# working.net
KiCad netlist of a schematic drawn in EAGLE
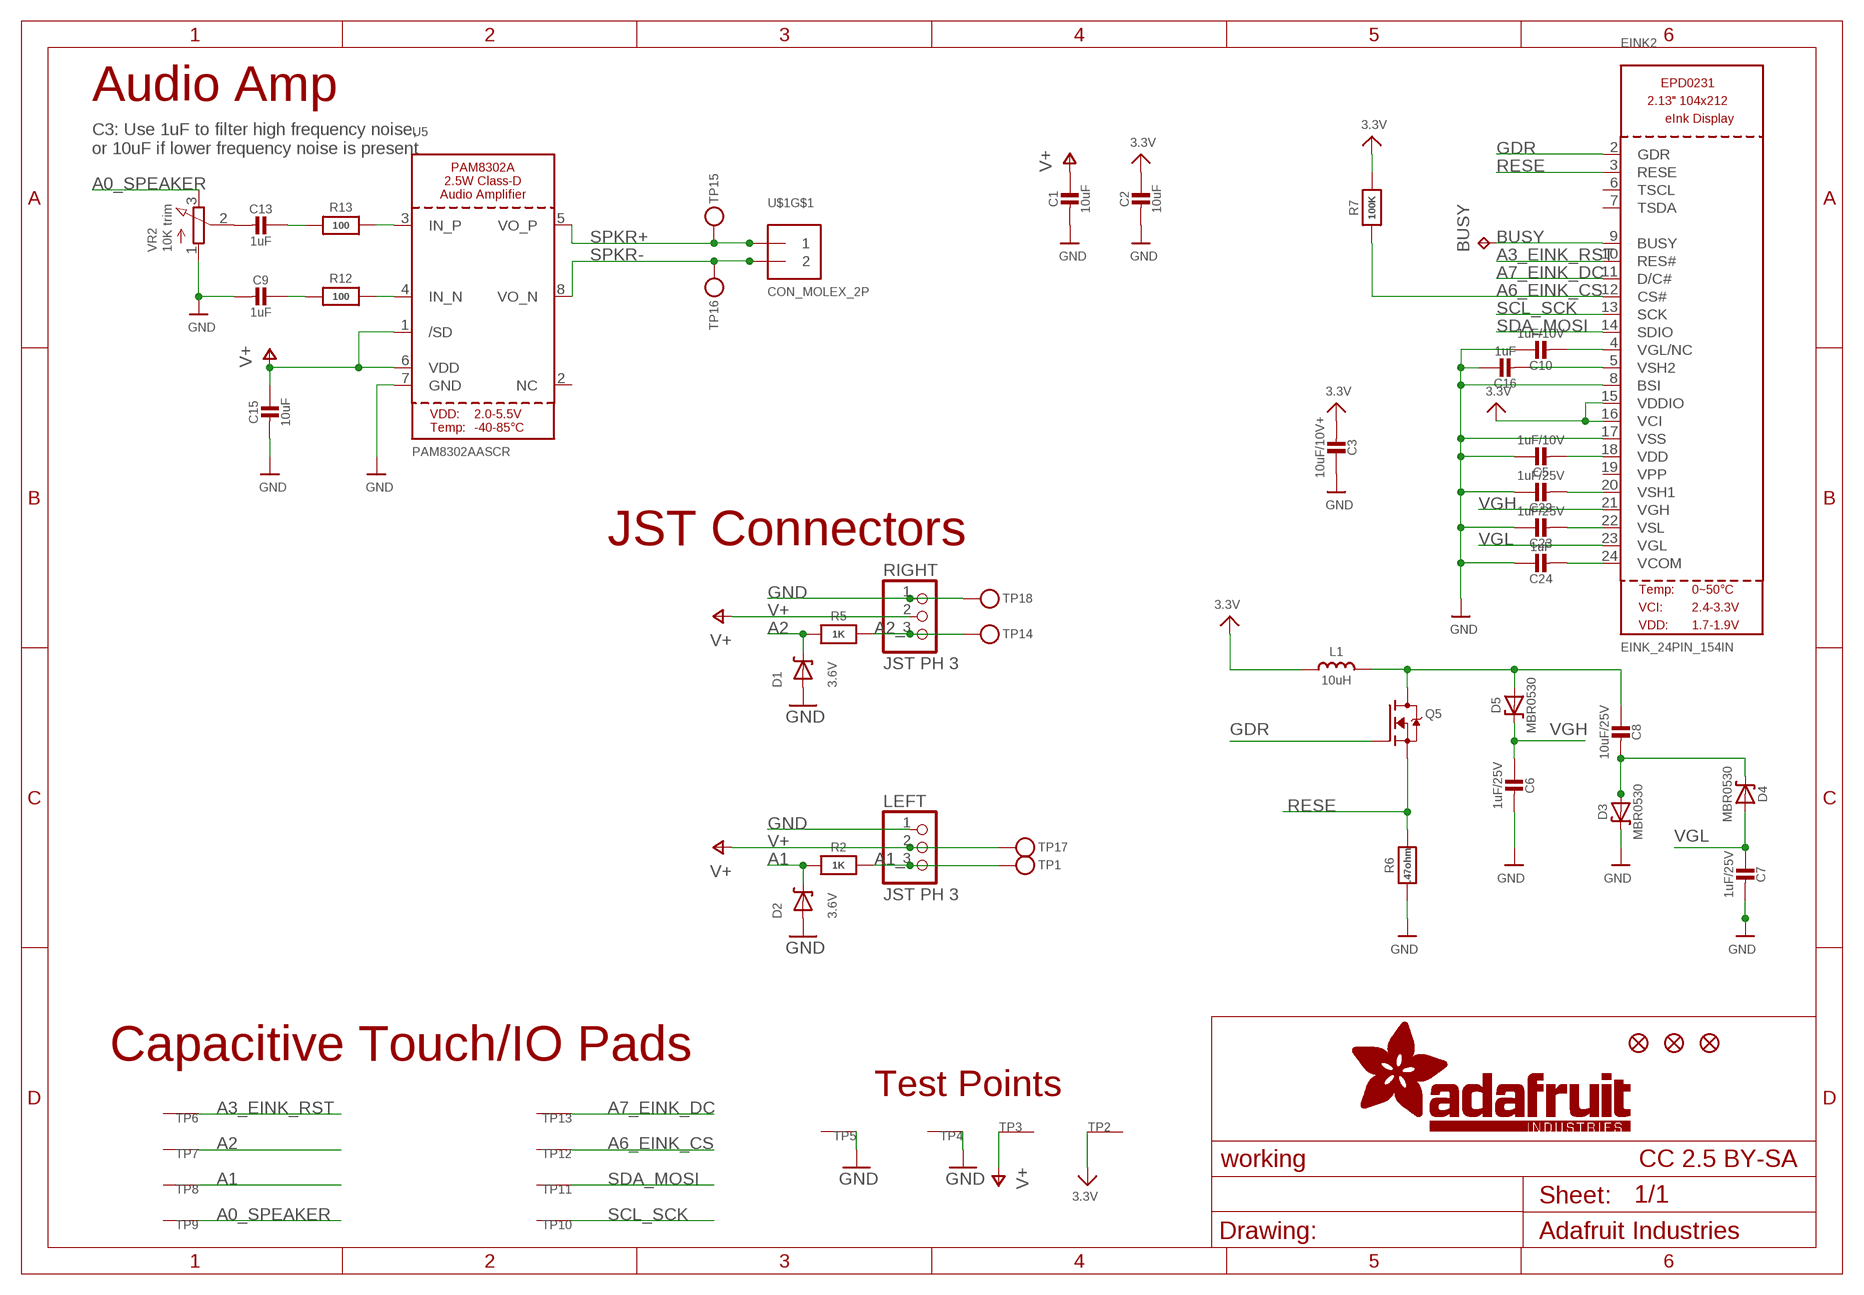
[diagram p0: schematic, sheet 1]

(export (version "E")
  (design (tool "Eeschema 10.0.6"))
  (components
    (comp (ref "BUSY")
      (value "TPTP15SQ")
      (footprint "eagle-import:TP15SQ")
      (libsource (lib "eagle-import") (part "TPTP15SQ"))
    )
    (comp (ref "C1")
      (value "10uF")
      (footprint "eagle-import:0805-NO")
      (libsource (lib "eagle-import") (part "CAP_CERAMIC0805-NOOUTLINE"))
    )
    (comp (ref "C2")
      (value "10uF")
      (footprint "eagle-import:0805-NO")
      (libsource (lib "eagle-import") (part "CAP_CERAMIC0805-NOOUTLINE"))
    )
    (comp (ref "C3")
      (value "10uF/10V+")
      (footprint "eagle-import:0805-NO")
      (libsource (lib "eagle-import") (part "CAP_CERAMIC0805-NOOUTLINE"))
    )
    (comp (ref "C5")
      (value "1uF/10V")
      (footprint "eagle-import:0805-NO")
      (libsource (lib "eagle-import") (part "CAP_CERAMIC0805-NOOUTLINE"))
    )
    (comp (ref "C6")
      (value "1uF/25V")
      (footprint "eagle-import:0805-NO")
      (libsource (lib "eagle-import") (part "CAP_CERAMIC0805-NOOUTLINE"))
    )
    (comp (ref "C7")
      (value "1uF/25V")
      (footprint "eagle-import:0805-NO")
      (libsource (lib "eagle-import") (part "CAP_CERAMIC0805-NOOUTLINE"))
    )
    (comp (ref "C8")
      (value "10uF/25V")
      (footprint "eagle-import:0805-NO")
      (libsource (lib "eagle-import") (part "CAP_CERAMIC0805-NOOUTLINE"))
    )
    (comp (ref "C9")
      (value "1uF")
      (footprint "eagle-import:0805-NO")
      (libsource (lib "eagle-import") (part "CAP_CERAMIC0805-NOOUTLINE"))
    )
    (comp (ref "C10")
      (value "1uF/10V")
      (footprint "eagle-import:0805-NO")
      (libsource (lib "eagle-import") (part "CAP_CERAMIC0805-NOOUTLINE"))
    )
    (comp (ref "C13")
      (value "1uF")
      (footprint "eagle-import:0805-NO")
      (libsource (lib "eagle-import") (part "CAP_CERAMIC0805-NOOUTLINE"))
    )
    (comp (ref "C15")
      (value "10uF")
      (footprint "eagle-import:0805-NO")
      (libsource (lib "eagle-import") (part "CAP_CERAMIC0805-NOOUTLINE"))
    )
    (comp (ref "C16")
      (value "1uF")
      (footprint "eagle-import:0805-NO")
      (libsource (lib "eagle-import") (part "CAP_CERAMIC0805-NOOUTLINE"))
    )
    (comp (ref "C22")
      (value "1uF/25V")
      (footprint "eagle-import:0805-NO")
      (libsource (lib "eagle-import") (part "CAP_CERAMIC0805-NOOUTLINE"))
    )
    (comp (ref "C23")
      (value "1uF/25V")
      (footprint "eagle-import:0805-NO")
      (libsource (lib "eagle-import") (part "CAP_CERAMIC0805-NOOUTLINE"))
    )
    (comp (ref "C24")
      (value "1uF")
      (footprint "eagle-import:0805-NO")
      (libsource (lib "eagle-import") (part "CAP_CERAMIC0805-NOOUTLINE"))
    )
    (comp (ref "D1")
      (value "3.6V")
      (footprint "eagle-import:SOD-323")
      (libsource (lib "eagle-import") (part "DIODE-ZENERSOD323"))
    )
    (comp (ref "D2")
      (value "3.6V")
      (footprint "eagle-import:SOD-323")
      (libsource (lib "eagle-import") (part "DIODE-ZENERSOD323"))
    )
    (comp (ref "D3")
      (value "MBR0530")
      (footprint "eagle-import:SOD-123")
      (libsource (lib "eagle-import") (part "DIODE-SCHOTTKYSOD-123"))
    )
    (comp (ref "D4")
      (value "MBR0530")
      (footprint "eagle-import:SOD-123")
      (libsource (lib "eagle-import") (part "DIODE-SCHOTTKYSOD-123"))
    )
    (comp (ref "D5")
      (value "MBR0530")
      (footprint "eagle-import:SOD-123")
      (libsource (lib "eagle-import") (part "DIODE-SCHOTTKYSOD-123"))
    )
    (comp (ref "EINK2")
      (value "EINK_24PIN_154IN")
      (footprint "eagle-import:EINK_154IN")
      (libsource (lib "eagle-import") (part "EINK_24PIN_154IN"))
    )
    (comp (ref "L1")
      (value "10uH")
      (footprint "eagle-import:INDUCTOR_4X4MM_NR401")
      (libsource (lib "eagle-import") (part "INDUCTORNR401"))
    )
    (comp (ref "LEFT")
      (value "JST PH 3")
      (footprint "eagle-import:JSTPH3")
      (libsource (lib "eagle-import") (part "CON_JST_PH_3PIN"))
    )
    (comp (ref "Q5")
      (value "IRLML0100")
      (footprint "eagle-import:SOT23-3")
      (libsource (lib "eagle-import") (part "IRLML2060TRPBF"))
    )
    (comp (ref "R2")
      (value "1K")
      (footprint "eagle-import:0603-NO")
      (libsource (lib "eagle-import") (part "RESISTOR_0603_NOOUT"))
    )
    (comp (ref "R5")
      (value "1K")
      (footprint "eagle-import:0603-NO")
      (libsource (lib "eagle-import") (part "RESISTOR_0603_NOOUT"))
    )
    (comp (ref "R6")
      (value ".47ohm")
      (footprint "eagle-import:0805_10MGAP")
      (libsource (lib "eagle-import") (part "RESISTOR0805_10MGAP"))
    )
    (comp (ref "R7")
      (value "100K")
      (footprint "eagle-import:0603-NO")
      (libsource (lib "eagle-import") (part "RESISTOR_0603_NOOUT"))
    )
    (comp (ref "R12")
      (value "100")
      (footprint "eagle-import:0603-NO")
      (libsource (lib "eagle-import") (part "RESISTOR_0603_NOOUT"))
    )
    (comp (ref "R13")
      (value "100")
      (footprint "eagle-import:0603-NO")
      (libsource (lib "eagle-import") (part "RESISTOR_0603_NOOUT"))
    )
    (comp (ref "RIGHT")
      (value "JST PH 3")
      (footprint "eagle-import:JSTPH3")
      (libsource (lib "eagle-import") (part "CON_JST_PH_3PIN"))
    )
    (comp (ref "TP1")
      (value "TESTPOINTROUND1.5MMNO")
      (footprint "eagle-import:TESTPOINT_ROUND_1.5MM_NO")
      (libsource (lib "eagle-import") (part "TESTPOINTROUND1.5MMNO"))
    )
    (comp (ref "TP2")
      (value "SEWTAP_SMTNUTM3")
      (footprint "eagle-import:SMT_NUT_3MM")
      (libsource (lib "eagle-import") (part "SEWTAP_SMTNUTM3"))
    )
    (comp (ref "TP3")
      (value "SEWTAP_SMTNUTM3")
      (footprint "eagle-import:SMT_NUT_3MM")
      (libsource (lib "eagle-import") (part "SEWTAP_SMTNUTM3"))
    )
    (comp (ref "TP4")
      (value "SEWTAP_SMTNUTM3")
      (footprint "eagle-import:SMT_NUT_3MM")
      (libsource (lib "eagle-import") (part "SEWTAP_SMTNUTM3"))
    )
    (comp (ref "TP5")
      (value "SEWTAP_SMTNUTM3")
      (footprint "eagle-import:SMT_NUT_3MM")
      (libsource (lib "eagle-import") (part "SEWTAP_SMTNUTM3"))
    )
    (comp (ref "TP6")
      (value "SEWTAP_SMTNUTM3")
      (footprint "eagle-import:SMT_NUT_3MM")
      (libsource (lib "eagle-import") (part "SEWTAP_SMTNUTM3"))
    )
    (comp (ref "TP7")
      (value "SEWTAP_SMTNUTM3")
      (footprint "eagle-import:SMT_NUT_3MM")
      (libsource (lib "eagle-import") (part "SEWTAP_SMTNUTM3"))
    )
    (comp (ref "TP8")
      (value "SEWTAP_SMTNUTM3")
      (footprint "eagle-import:SMT_NUT_3MM")
      (libsource (lib "eagle-import") (part "SEWTAP_SMTNUTM3"))
    )
    (comp (ref "TP9")
      (value "SEWTAP_SMTNUTM3")
      (footprint "eagle-import:SMT_NUT_3MM")
      (libsource (lib "eagle-import") (part "SEWTAP_SMTNUTM3"))
    )
    (comp (ref "TP10")
      (value "SEWTAP_SMTNUTM3")
      (footprint "eagle-import:SMT_NUT_3MM")
      (libsource (lib "eagle-import") (part "SEWTAP_SMTNUTM3"))
    )
    (comp (ref "TP11")
      (value "SEWTAP_SMTNUTM3")
      (footprint "eagle-import:SMT_NUT_3MM")
      (libsource (lib "eagle-import") (part "SEWTAP_SMTNUTM3"))
    )
    (comp (ref "TP12")
      (value "SEWTAP_SMTNUTM3")
      (footprint "eagle-import:SMT_NUT_3MM")
      (libsource (lib "eagle-import") (part "SEWTAP_SMTNUTM3"))
    )
    (comp (ref "TP13")
      (value "SEWTAP_SMTNUTM3")
      (footprint "eagle-import:SMT_NUT_3MM")
      (libsource (lib "eagle-import") (part "SEWTAP_SMTNUTM3"))
    )
    (comp (ref "TP14")
      (value "TESTPOINTROUND1.5MMNO")
      (footprint "eagle-import:TESTPOINT_ROUND_1.5MM_NO")
      (libsource (lib "eagle-import") (part "TESTPOINTROUND1.5MMNO"))
    )
    (comp (ref "TP15")
      (value "TESTPOINTROUND1.5MMNO")
      (footprint "eagle-import:TESTPOINT_ROUND_1.5MM_NO")
      (libsource (lib "eagle-import") (part "TESTPOINTROUND1.5MMNO"))
    )
    (comp (ref "TP16")
      (value "TESTPOINTROUND1.5MMNO")
      (footprint "eagle-import:TESTPOINT_ROUND_1.5MM_NO")
      (libsource (lib "eagle-import") (part "TESTPOINTROUND1.5MMNO"))
    )
    (comp (ref "TP17")
      (value "TESTPOINTROUND1.5MMNO")
      (footprint "eagle-import:TESTPOINT_ROUND_1.5MM_NO")
      (libsource (lib "eagle-import") (part "TESTPOINTROUND1.5MMNO"))
    )
    (comp (ref "TP18")
      (value "TESTPOINTROUND1.5MMNO")
      (footprint "eagle-import:TESTPOINT_ROUND_1.5MM_NO")
      (libsource (lib "eagle-import") (part "TESTPOINTROUND1.5MMNO"))
    )
    (comp (ref "U$1")
      (value "CON_MOLEX_2P")
      (footprint "eagle-import:53398-0271")
      (libsource (lib "eagle-import") (part "CON_MOLEX_2P"))
    )
    (comp (ref "U$2")
      (value "FIDUCIAL_1MM")
      (footprint "eagle-import:FIDUCIAL_1MM")
      (libsource (lib "eagle-import") (part "FIDUCIAL_1MM"))
    )
    (comp (ref "U$3")
      (value "FIDUCIAL_1MM")
      (footprint "eagle-import:FIDUCIAL_1MM")
      (fields (field (name "BOM") "EXCLUDE"))
      (libsource (lib "eagle-import") (part "FIDUCIAL_1MM"))
    )
    (comp (ref "U$6")
      (value "FIDUCIAL_1MM")
      (footprint "eagle-import:FIDUCIAL_1MM")
      (libsource (lib "eagle-import") (part "FIDUCIAL_1MM"))
    )
    (comp (ref "U5")
      (value "PAM8302AASCR")
      (footprint "eagle-import:MSOP8_0.65MM")
      (libsource (lib "eagle-import") (part "AUDIOAMP_PAM8302A"))
    )
    (comp (ref "VR2")
      (value "10K trim")
      (footprint "eagle-import:TRIMPOT_BOURNS_3303W")
      (libsource (lib "eagle-import") (part "TRIMPOT3303W/X"))
    )
  )
  (nets
    (net (code "1") (name "/A0_SPEAKER") (class "Default")
      (node (ref "TP9") (pin "P$1") (pinfunction "SEW_P$1") (pintype "bidirectional"))
      (node (ref "VR2") (pin "3") (pinfunction "E_3") (pintype "passive"))
    )
    (net (code "2") (name "/A1") (class "Default")
      (node (ref "D2") (pin "C") (pinfunction "C_C") (pintype "passive"))
      (node (ref "R2") (pin "2") (pinfunction "2_2") (pintype "passive"))
      (node (ref "TP8") (pin "P$1") (pinfunction "SEW_P$1") (pintype "bidirectional"))
    )
    (net (code "3") (name "/A1_") (class "Default")
      (node (ref "LEFT") (pin "3") (pinfunction "3_3") (pintype "passive"))
      (node (ref "R2") (pin "1") (pinfunction "1_1") (pintype "passive"))
      (node (ref "TP1") (pin "P$1") (pinfunction "P$1_P$1") (pintype "bidirectional"))
    )
    (net (code "4") (name "/A2") (class "Default")
      (node (ref "D1") (pin "C") (pinfunction "C_C") (pintype "passive"))
      (node (ref "R5") (pin "2") (pinfunction "2_2") (pintype "passive"))
      (node (ref "TP7") (pin "P$1") (pinfunction "SEW_P$1") (pintype "bidirectional"))
    )
    (net (code "5") (name "/A2_") (class "Default")
      (node (ref "R5") (pin "1") (pinfunction "1_1") (pintype "passive"))
      (node (ref "RIGHT") (pin "3") (pinfunction "3_3") (pintype "passive"))
      (node (ref "TP14") (pin "P$1") (pinfunction "P$1_P$1") (pintype "bidirectional"))
    )
    (net (code "6") (name "/A3_EINK_RST") (class "Default")
      (node (ref "EINK2") (pin "10") (pinfunction "RES#_10") (pintype "input"))
      (node (ref "TP6") (pin "P$1") (pinfunction "SEW_P$1") (pintype "bidirectional"))
    )
    (net (code "7") (name "/A6_EINK_CS") (class "Default")
      (node (ref "EINK2") (pin "12") (pinfunction "CS#_12") (pintype "input"))
      (node (ref "R7") (pin "1") (pinfunction "1_1") (pintype "passive"))
      (node (ref "TP12") (pin "P$1") (pinfunction "SEW_P$1") (pintype "bidirectional"))
    )
    (net (code "8") (name "/A7_EINK_DC") (class "Default")
      (node (ref "EINK2") (pin "11") (pinfunction "D/C#_11") (pintype "input"))
      (node (ref "TP13") (pin "P$1") (pinfunction "SEW_P$1") (pintype "bidirectional"))
    )
    (net (code "9") (name "/BUSY") (class "Default")
      (node (ref "BUSY") (pin "TP") (pinfunction "TP_TP") (pintype "input"))
      (node (ref "EINK2") (pin "9") (pinfunction "BUSY_9") (pintype "output"))
    )
    (net (code "10") (name "/GDR") (class "Default")
      (node (ref "EINK2") (pin "2") (pinfunction "GDR_2") (pintype "output"))
      (node (ref "Q5") (pin "1") (pinfunction "G_1") (pintype "bidirectional"))
    )
    (net (code "11") (name "/RESE") (class "Default")
      (node (ref "EINK2") (pin "3") (pinfunction "RESE_3") (pintype "input"))
      (node (ref "Q5") (pin "2") (pinfunction "S_2") (pintype "bidirectional"))
      (node (ref "R6") (pin "1") (pinfunction "1_1") (pintype "passive"))
    )
    (net (code "12") (name "/SCL_SCK") (class "Default")
      (node (ref "EINK2") (pin "13") (pinfunction "SCK_13") (pintype "bidirectional"))
      (node (ref "TP10") (pin "P$1") (pinfunction "SEW_P$1") (pintype "bidirectional"))
    )
    (net (code "13") (name "/SDA_MOSI") (class "Default")
      (node (ref "EINK2") (pin "14") (pinfunction "SDIO_14") (pintype "bidirectional"))
      (node (ref "TP11") (pin "P$1") (pinfunction "SEW_P$1") (pintype "bidirectional"))
    )
    (net (code "14") (name "/SPKR+") (class "Default")
      (node (ref "TP15") (pin "P$1") (pinfunction "P$1_P$1") (pintype "bidirectional"))
      (node (ref "U$1") (pin "1") (pinfunction "1_1") (pintype "passive"))
      (node (ref "U5") (pin "5") (pinfunction "VO_P_5") (pintype "output"))
    )
    (net (code "15") (name "/SPKR-") (class "Default")
      (node (ref "TP16") (pin "P$1") (pinfunction "P$1_P$1") (pintype "bidirectional"))
      (node (ref "U$1") (pin "2") (pinfunction "2_2") (pintype "passive"))
      (node (ref "U5") (pin "8") (pinfunction "VO_N_8") (pintype "output"))
    )
    (net (code "16") (name "/VGH") (class "Default")
      (node (ref "C6") (pin "1") (pinfunction "1_1") (pintype "passive"))
      (node (ref "D5") (pin "C") (pinfunction "C_C") (pintype "passive"))
      (node (ref "EINK2") (pin "21") (pinfunction "VGH_21") (pintype "passive"))
    )
    (net (code "17") (name "/VGL") (class "Default")
      (node (ref "C7") (pin "1") (pinfunction "1_1") (pintype "passive"))
      (node (ref "D4") (pin "A") (pinfunction "A_A") (pintype "passive"))
      (node (ref "EINK2") (pin "23") (pinfunction "VGL_23") (pintype "passive"))
    )
    (net (code "18") (name "3.3V") (class "Default")
      (node (ref "C2") (pin "1") (pinfunction "1_1") (pintype "passive"))
      (node (ref "C3") (pin "2") (pinfunction "2_2") (pintype "passive"))
      (node (ref "EINK2") (pin "15") (pinfunction "VDDIO_15") (pintype "power_in"))
      (node (ref "EINK2") (pin "16") (pinfunction "VCI_16") (pintype "power_in"))
      (node (ref "L1") (pin "P$2") (pinfunction "2_P$2") (pintype "passive"))
      (node (ref "R7") (pin "2") (pinfunction "2_2") (pintype "passive"))
      (node (ref "TP2") (pin "P$1") (pinfunction "SEW_P$1") (pintype "bidirectional"))
    )
    (net (code "19") (name "GND") (class "Default")
      (node (ref "C1") (pin "2") (pinfunction "2_2") (pintype "passive"))
      (node (ref "C10") (pin "1") (pinfunction "1_1") (pintype "passive"))
      (node (ref "C15") (pin "2") (pinfunction "2_2") (pintype "passive"))
      (node (ref "C16") (pin "1") (pinfunction "1_1") (pintype "passive"))
      (node (ref "C2") (pin "2") (pinfunction "2_2") (pintype "passive"))
      (node (ref "C22") (pin "1") (pinfunction "1_1") (pintype "passive"))
      (node (ref "C23") (pin "1") (pinfunction "1_1") (pintype "passive"))
      (node (ref "C24") (pin "1") (pinfunction "1_1") (pintype "passive"))
      (node (ref "C3") (pin "1") (pinfunction "1_1") (pintype "passive"))
      (node (ref "C5") (pin "1") (pinfunction "1_1") (pintype "passive"))
      (node (ref "C6") (pin "2") (pinfunction "2_2") (pintype "passive"))
      (node (ref "C7") (pin "2") (pinfunction "2_2") (pintype "passive"))
      (node (ref "C9") (pin "2") (pinfunction "2_2") (pintype "passive"))
      (node (ref "D1") (pin "A") (pinfunction "A_A") (pintype "passive"))
      (node (ref "D2") (pin "A") (pinfunction "A_A") (pintype "passive"))
      (node (ref "D3") (pin "C") (pinfunction "C_C") (pintype "passive"))
      (node (ref "EINK2") (pin "17") (pinfunction "VSS_17") (pintype "power_in"))
      (node (ref "EINK2") (pin "8") (pinfunction "BSI_8") (pintype "input"))
      (node (ref "LEFT") (pin "1") (pinfunction "1_1") (pintype "passive"))
      (node (ref "R6") (pin "2") (pinfunction "2_2") (pintype "passive"))
      (node (ref "RIGHT") (pin "1") (pinfunction "1_1") (pintype "passive"))
      (node (ref "TP18") (pin "P$1") (pinfunction "P$1_P$1") (pintype "bidirectional"))
      (node (ref "TP4") (pin "P$1") (pinfunction "SEW_P$1") (pintype "bidirectional"))
      (node (ref "TP5") (pin "P$1") (pinfunction "SEW_P$1") (pintype "bidirectional"))
      (node (ref "U5") (pin "7") (pinfunction "GND_7") (pintype "power_in"))
      (node (ref "VR2") (pin "1") (pinfunction "A_1") (pintype "passive"))
    )
    (net (code "20") (name "Net-(C8-Pad2)") (class "Default")
      (node (ref "C8") (pin "2") (pinfunction "2_2") (pintype "passive"))
      (node (ref "D3") (pin "A") (pinfunction "A_A") (pintype "passive"))
      (node (ref "D4") (pin "C") (pinfunction "C_C") (pintype "passive"))
    )
    (net (code "21") (name "Net-(C9-Pad1)") (class "Default")
      (node (ref "C9") (pin "1") (pinfunction "1_1") (pintype "passive"))
      (node (ref "R12") (pin "1") (pinfunction "1_1") (pintype "passive"))
    )
    (net (code "22") (name "Net-(C13-Pad1)") (class "Default")
      (node (ref "C13") (pin "1") (pinfunction "1_1") (pintype "passive"))
      (node (ref "R13") (pin "1") (pinfunction "1_1") (pintype "passive"))
    )
    (net (code "23") (name "Net-(EINK2-VCOM)") (class "Default")
      (node (ref "C24") (pin "2") (pinfunction "2_2") (pintype "passive"))
      (node (ref "EINK2") (pin "24") (pinfunction "VCOM_24") (pintype "passive"))
    )
    (net (code "24") (name "Net-(EINK2-VDD)") (class "Default")
      (node (ref "C5") (pin "2") (pinfunction "2_2") (pintype "passive"))
      (node (ref "EINK2") (pin "18") (pinfunction "VDD_18") (pintype "passive"))
    )
    (net (code "25") (name "Net-(EINK2-VGL{slash}NC)") (class "Default")
      (node (ref "C10") (pin "2") (pinfunction "2_2") (pintype "passive"))
      (node (ref "EINK2") (pin "4") (pinfunction "VGL/NC_4") (pintype "bidirectional"))
    )
    (net (code "26") (name "Net-(EINK2-VSH1)") (class "Default")
      (node (ref "C22") (pin "2") (pinfunction "2_2") (pintype "passive"))
      (node (ref "EINK2") (pin "20") (pinfunction "VSH1_20") (pintype "passive"))
    )
    (net (code "27") (name "Net-(EINK2-VSH2)") (class "Default")
      (node (ref "C16") (pin "2") (pinfunction "2_2") (pintype "passive"))
      (node (ref "EINK2") (pin "5") (pinfunction "VSH2_5") (pintype "passive"))
    )
    (net (code "28") (name "Net-(EINK2-VSL)") (class "Default")
      (node (ref "C23") (pin "2") (pinfunction "2_2") (pintype "passive"))
      (node (ref "EINK2") (pin "22") (pinfunction "VSL_22") (pintype "passive"))
    )
    (net (code "29") (name "Net-(L1-1)") (class "Default")
      (node (ref "C8") (pin "1") (pinfunction "1_1") (pintype "passive"))
      (node (ref "D5") (pin "A") (pinfunction "A_A") (pintype "passive"))
      (node (ref "L1") (pin "P$1") (pinfunction "1_P$1") (pintype "passive"))
      (node (ref "Q5") (pin "3") (pinfunction "D_3") (pintype "bidirectional"))
    )
    (net (code "30") (name "Net-(U5-IN_N)") (class "Default")
      (node (ref "R12") (pin "2") (pinfunction "2_2") (pintype "passive"))
      (node (ref "U5") (pin "4") (pinfunction "IN_N_4") (pintype "input"))
    )
    (net (code "31") (name "Net-(U5-IN_P)") (class "Default")
      (node (ref "R13") (pin "2") (pinfunction "2_2") (pintype "passive"))
      (node (ref "U5") (pin "3") (pinfunction "IN_P_3") (pintype "input"))
    )
    (net (code "32") (name "Net-(VR2-S)") (class "Default")
      (node (ref "C13") (pin "2") (pinfunction "2_2") (pintype "passive"))
      (node (ref "VR2") (pin "2") (pinfunction "S_2") (pintype "passive"))
    )
    (net (code "33") (name "V+") (class "Default")
      (node (ref "C1") (pin "1") (pinfunction "1_1") (pintype "passive"))
      (node (ref "C15") (pin "1") (pinfunction "1_1") (pintype "passive"))
      (node (ref "LEFT") (pin "2") (pinfunction "2_2") (pintype "passive"))
      (node (ref "RIGHT") (pin "2") (pinfunction "2_2") (pintype "passive"))
      (node (ref "TP17") (pin "P$1") (pinfunction "P$1_P$1") (pintype "bidirectional"))
      (node (ref "TP3") (pin "P$1") (pinfunction "SEW_P$1") (pintype "bidirectional"))
      (node (ref "U5") (pin "1") (pinfunction "/SD_1") (pintype "input"))
      (node (ref "U5") (pin "6") (pinfunction "VDD_6") (pintype "power_in"))
    )
    (net (code "34") (name "unconnected-(EINK2-TSCL-Pad6)") (class "Default")
      (node (ref "EINK2") (pin "6") (pinfunction "TSCL_6") (pintype "output"))
    )
    (net (code "35") (name "unconnected-(EINK2-TSDA-Pad7)") (class "Default")
      (node (ref "EINK2") (pin "7") (pinfunction "TSDA_7") (pintype "bidirectional"))
    )
    (net (code "36") (name "unconnected-(EINK2-VPP-Pad19)") (class "Default")
      (node (ref "EINK2") (pin "19") (pinfunction "VPP_19") (pintype "passive"))
    )
    (net (code "37") (name "unconnected-(U5-NC-Pad2)") (class "Default")
      (node (ref "U5") (pin "2") (pinfunction "NC_2") (pintype "no_connect"))
    )
  )
)
